# untitled.net
KiCad netlist of a schematic drawn in EAGLE
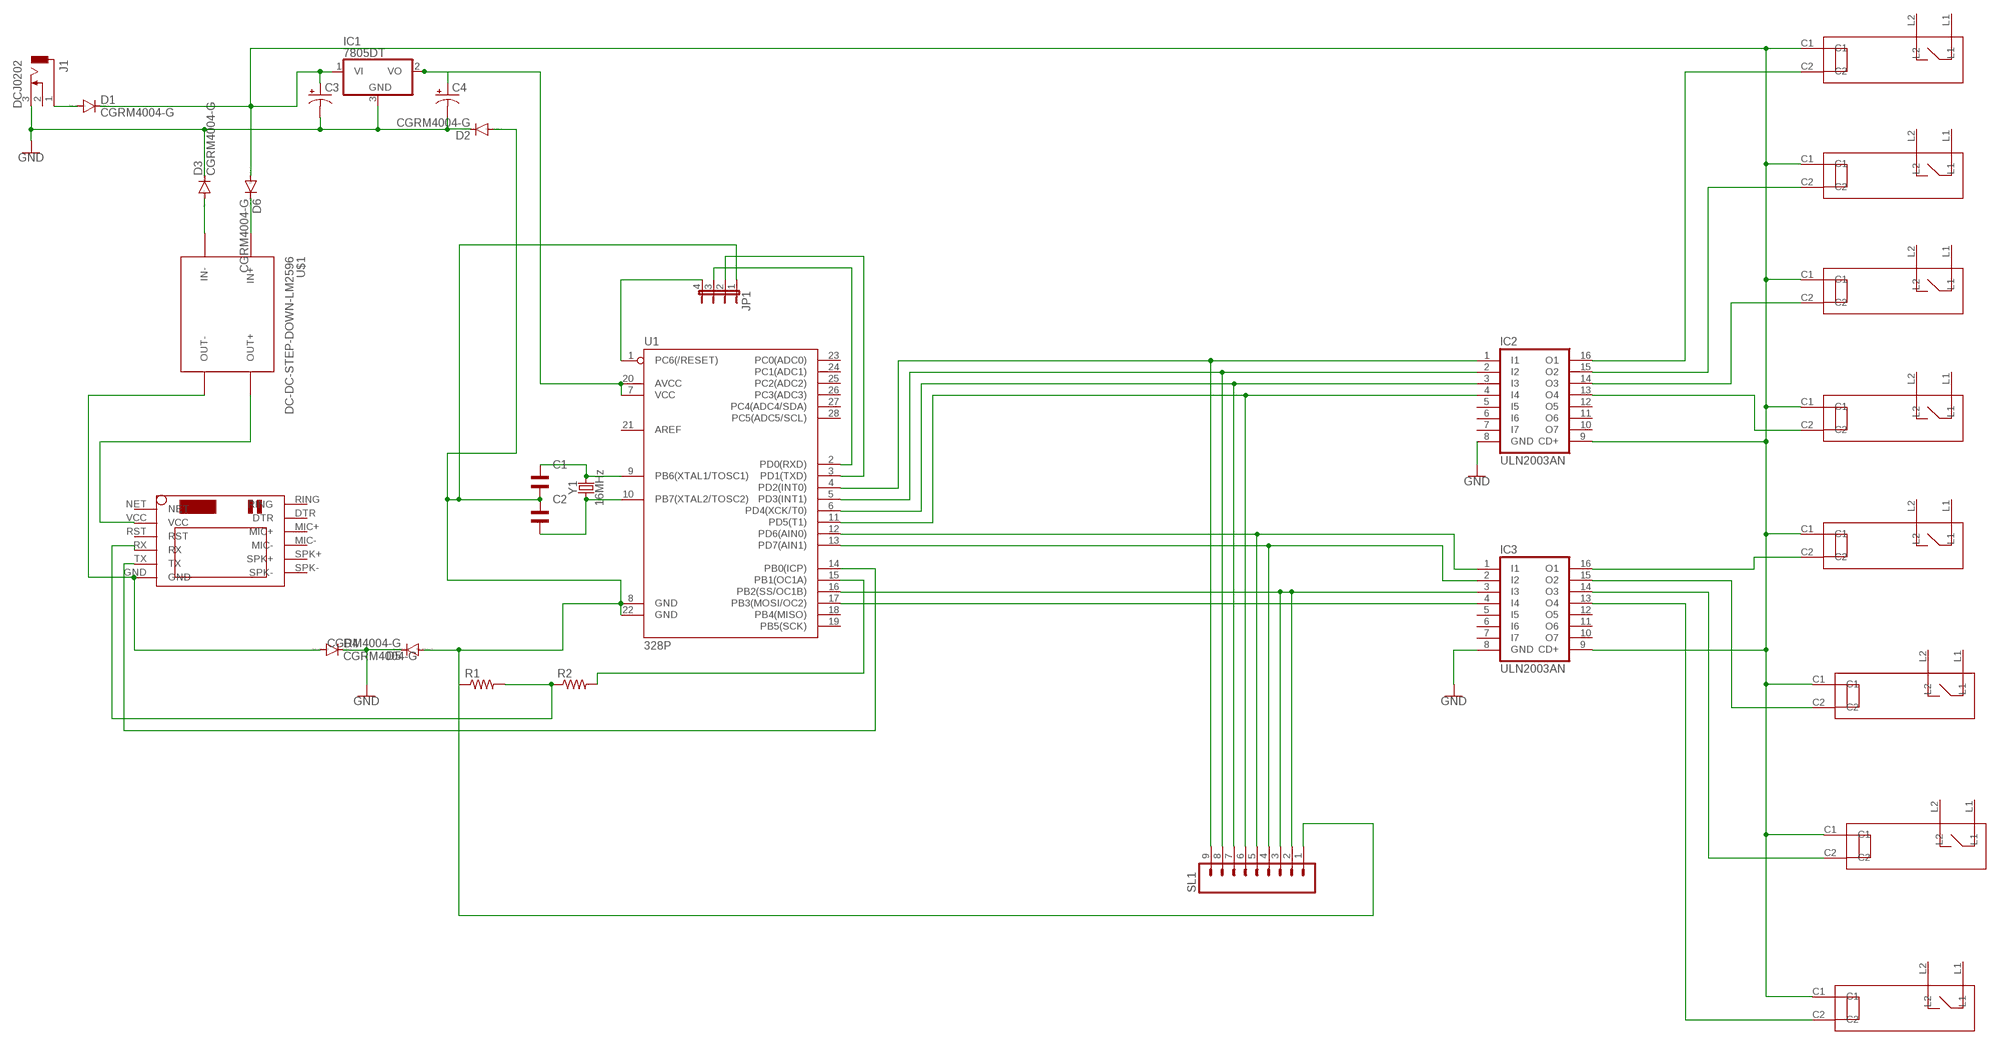
[diagram p0: schematic, sheet 1]

(export (version "E")
  (design (tool "Eeschema 10.0.6"))
  (components
    (comp (ref "C1")
      (value "WCAP-CSGP_1206_885012008001")
      (footprint "eagle-import:WCAP-CSGP_1206")
      (libsource (lib "eagle-import") (part "WCAP-CSGP_1206_885012008001"))
    )
    (comp (ref "C2")
      (value "WCAP-CSGP_1206_885012008001")
      (footprint "eagle-import:WCAP-CSGP_1206")
      (libsource (lib "eagle-import") (part "WCAP-CSGP_1206_885012008001"))
    )
    (comp (ref "C3")
      (value "CPOL-USE3.5-8")
      (footprint "eagle-import:E3,5-8")
      (libsource (lib "eagle-import") (part "CPOL-USE3.5-8"))
    )
    (comp (ref "C4")
      (value "CPOL-USE2.5-5")
      (footprint "eagle-import:E2,5-5")
      (libsource (lib "eagle-import") (part "CPOL-USE2.5-5"))
    )
    (comp (ref "D1")
      (value "CGRM4004-G")
      (footprint "eagle-import:SOD-123_MINI-SMA")
      (libsource (lib "eagle-import") (part "CGRM400-G4"))
    )
    (comp (ref "D2")
      (value "CGRM4004-G")
      (footprint "eagle-import:SOD-123_MINI-SMA")
      (libsource (lib "eagle-import") (part "CGRM400-G4"))
    )
    (comp (ref "D3")
      (value "CGRM4004-G")
      (footprint "eagle-import:SOD-123_MINI-SMA")
      (libsource (lib "eagle-import") (part "CGRM400-G4"))
    )
    (comp (ref "D4")
      (value "CGRM4004-G")
      (footprint "eagle-import:SOD-123_MINI-SMA")
      (libsource (lib "eagle-import") (part "CGRM400-G4"))
    )
    (comp (ref "D5")
      (value "CGRM4004-G")
      (footprint "eagle-import:SOD-123_MINI-SMA")
      (libsource (lib "eagle-import") (part "CGRM400-G4"))
    )
    (comp (ref "D6")
      (value "CGRM4004-G")
      (footprint "eagle-import:SOD-123_MINI-SMA")
      (libsource (lib "eagle-import") (part "CGRM400-G4"))
    )
    (comp (ref "IC1")
      (value "7805DT")
      (footprint "eagle-import:TO252")
      (libsource (lib "eagle-import") (part "78DT05"))
    )
    (comp (ref "IC2")
      (value "ULN2003AN")
      (footprint "eagle-import:DIL16")
      (libsource (lib "eagle-import") (part "ULN2003AN"))
    )
    (comp (ref "IC3")
      (value "ULN2003AN")
      (footprint "eagle-import:DIL16")
      (libsource (lib "eagle-import") (part "ULN2003AN"))
    )
    (comp (ref "J1")
      (value "DCJ0202")
      (footprint "eagle-import:DCJ0202")
      (libsource (lib "eagle-import") (part "DCJ0202"))
    )
    (comp (ref "JP1")
      (value "JP4E")
      (footprint "eagle-import:JP4")
      (libsource (lib "eagle-import") (part "JP4E"))
    )
    (comp (ref "R1")
      (value "R-US_R1206")
      (footprint "eagle-import:R1206")
      (libsource (lib "eagle-import") (part "R-US_R1206"))
    )
    (comp (ref "R2")
      (value "R-US_R1206")
      (footprint "eagle-import:R1206")
      (libsource (lib "eagle-import") (part "R-US_R1206"))
    )
    (comp (ref "SL1")
      (value "M09")
      (footprint "eagle-import:09P")
      (libsource (lib "eagle-import") (part "M09"))
    )
    (comp (ref "U$1")
      (value "DC-DC-STEP-DOWN-LM2596")
      (footprint "eagle-import:DC-DC-STEP-DOWN-LM2596")
      (libsource (lib "eagle-import") (part "DC-DC-STEP-DOWN-LM2596"))
    )
    (comp (ref "U$2")
      (value "SIM800LMODULE")
      (footprint "eagle-import:SIM800LMODULE")
      (libsource (lib "eagle-import") (part "SIM800LMODULE"))
    )
    (comp (ref "U$3")
      (value "HF46F")
      (footprint "eagle-import:HF46F")
      (libsource (lib "eagle-import") (part "HF46F"))
    )
    (comp (ref "U$4")
      (value "HF46F")
      (footprint "eagle-import:HF46F")
      (libsource (lib "eagle-import") (part "HF46F"))
    )
    (comp (ref "U$5")
      (value "HF46F")
      (footprint "eagle-import:HF46F")
      (libsource (lib "eagle-import") (part "HF46F"))
    )
    (comp (ref "U$6")
      (value "HF46F")
      (footprint "eagle-import:HF46F")
      (libsource (lib "eagle-import") (part "HF46F"))
    )
    (comp (ref "U$7")
      (value "HF46F")
      (footprint "eagle-import:HF46F")
      (libsource (lib "eagle-import") (part "HF46F"))
    )
    (comp (ref "U$8")
      (value "HF46F")
      (footprint "eagle-import:HF46F")
      (libsource (lib "eagle-import") (part "HF46F"))
    )
    (comp (ref "U$9")
      (value "HF46F")
      (footprint "eagle-import:HF46F")
      (libsource (lib "eagle-import") (part "HF46F"))
    )
    (comp (ref "U$10")
      (value "HF46F")
      (footprint "eagle-import:HF46F")
      (libsource (lib "eagle-import") (part "HF46F"))
    )
    (comp (ref "U1")
      (value "328P")
      (footprint "eagle-import:DIP28")
      (libsource (lib "eagle-import") (part "ATMEGA328P_PDIP"))
    )
    (comp (ref "Y1")
      (value "16MHz")
      (footprint "eagle-import:HC49US")
      (libsource (lib "eagle-import") (part "CRYSTAL-16MHZPTH-HC49US"))
    )
  )
  (nets
    (net (code "1") (name "GND") (class "Default")
      (node (ref "C3") (pin "-") (pinfunction "-_-") (pintype "passive"))
      (node (ref "C4") (pin "-") (pinfunction "-_-") (pintype "passive"))
      (node (ref "D2") (pin "C") (pinfunction "C_C") (pintype "passive"))
      (node (ref "D3") (pin "C") (pinfunction "C_C") (pintype "passive"))
      (node (ref "D4") (pin "C") (pinfunction "C_C") (pintype "passive"))
      (node (ref "D5") (pin "C") (pinfunction "C_C") (pintype "passive"))
      (node (ref "IC1") (pin "3") (pinfunction "GND_3") (pintype "passive"))
      (node (ref "IC2") (pin "8") (pinfunction "GND_8") (pintype "power_in"))
      (node (ref "IC3") (pin "8") (pinfunction "GND_8") (pintype "power_in"))
      (node (ref "J1") (pin "3") (pinfunction "3_3") (pintype "passive"))
    )
    (net (code "2") (name "Net-(C1-Pad1)") (class "Default")
      (node (ref "C1") (pin "1") (pinfunction "1_1") (pintype "passive"))
      (node (ref "C2") (pin "2") (pinfunction "2_2") (pintype "passive"))
      (node (ref "D2") (pin "A") (pinfunction "A_A") (pintype "passive"))
      (node (ref "D5") (pin "A") (pinfunction "A_A") (pintype "passive"))
      (node (ref "JP1") (pin "1") (pinfunction "1_1") (pintype "passive"))
      (node (ref "R1") (pin "1") (pinfunction "1_1") (pintype "passive"))
      (node (ref "SL1") (pin "1") (pinfunction "1_1") (pintype "passive"))
      (node (ref "U1") (pin "22") (pinfunction "GND_22") (pintype "bidirectional"))
      (node (ref "U1") (pin "8") (pinfunction "GND_8") (pintype "bidirectional"))
    )
    (net (code "3") (name "Net-(D1-PadA)") (class "Default")
      (node (ref "D1") (pin "A") (pinfunction "A_A") (pintype "passive"))
      (node (ref "J1") (pin "1") (pinfunction "1_1") (pintype "passive"))
    )
    (net (code "4") (name "Net-(D3-PadA)") (class "Default")
      (node (ref "D3") (pin "A") (pinfunction "A_A") (pintype "passive"))
      (node (ref "U$1") (pin "IN-") (pinfunction "IN-_IN-") (pintype "bidirectional"))
    )
    (net (code "5") (name "Net-(D4-PadA)") (class "Default")
      (node (ref "D4") (pin "A") (pinfunction "A_A") (pintype "passive"))
      (node (ref "U$1") (pin "OUT-") (pinfunction "OUT-_OUT-") (pintype "bidirectional"))
      (node (ref "U$2") (pin "GND") (pinfunction "GND_GND") (pintype "bidirectional"))
    )
    (net (code "6") (name "Net-(D6-PadC)") (class "Default")
      (node (ref "D6") (pin "C") (pinfunction "C_C") (pintype "passive"))
      (node (ref "U$1") (pin "IN+") (pinfunction "IN+_IN+") (pintype "bidirectional"))
    )
    (net (code "7") (name "Net-(IC1-VI)") (class "Default")
      (node (ref "C3") (pin "+") (pinfunction "+_+") (pintype "passive"))
      (node (ref "D1") (pin "C") (pinfunction "C_C") (pintype "passive"))
      (node (ref "D6") (pin "A") (pinfunction "A_A") (pintype "passive"))
      (node (ref "IC1") (pin "1") (pinfunction "VI_1") (pintype "input"))
      (node (ref "IC2") (pin "9") (pinfunction "CD+_9") (pintype "passive"))
      (node (ref "IC3") (pin "9") (pinfunction "CD+_9") (pintype "passive"))
      (node (ref "U$10") (pin "C1") (pinfunction "C1_C1") (pintype "bidirectional"))
      (node (ref "U$3") (pin "C1") (pinfunction "C1_C1") (pintype "bidirectional"))
      (node (ref "U$4") (pin "C1") (pinfunction "C1_C1") (pintype "bidirectional"))
      (node (ref "U$5") (pin "C1") (pinfunction "C1_C1") (pintype "bidirectional"))
      (node (ref "U$6") (pin "C1") (pinfunction "C1_C1") (pintype "bidirectional"))
      (node (ref "U$7") (pin "C1") (pinfunction "C1_C1") (pintype "bidirectional"))
      (node (ref "U$8") (pin "C1") (pinfunction "C1_C1") (pintype "bidirectional"))
      (node (ref "U$9") (pin "C1") (pinfunction "C1_C1") (pintype "bidirectional"))
    )
    (net (code "8") (name "Net-(IC1-VO)") (class "Default")
      (node (ref "C4") (pin "+") (pinfunction "+_+") (pintype "passive"))
      (node (ref "IC1") (pin "2") (pinfunction "VO_2") (pintype "passive"))
      (node (ref "U1") (pin "20") (pinfunction "AVCC_20") (pintype "bidirectional"))
      (node (ref "U1") (pin "7") (pinfunction "VCC_7") (pintype "bidirectional"))
    )
    (net (code "9") (name "Net-(IC2-I1)") (class "Default")
      (node (ref "IC2") (pin "1") (pinfunction "I1_1") (pintype "input"))
      (node (ref "SL1") (pin "9") (pinfunction "9_9") (pintype "passive"))
      (node (ref "U1") (pin "4") (pinfunction "PD2(INT0)_4") (pintype "bidirectional"))
    )
    (net (code "10") (name "Net-(IC2-I2)") (class "Default")
      (node (ref "IC2") (pin "2") (pinfunction "I2_2") (pintype "input"))
      (node (ref "SL1") (pin "8") (pinfunction "8_8") (pintype "passive"))
      (node (ref "U1") (pin "5") (pinfunction "PD3(INT1)_5") (pintype "bidirectional"))
    )
    (net (code "11") (name "Net-(IC2-I3)") (class "Default")
      (node (ref "IC2") (pin "3") (pinfunction "I3_3") (pintype "input"))
      (node (ref "SL1") (pin "7") (pinfunction "7_7") (pintype "passive"))
      (node (ref "U1") (pin "6") (pinfunction "PD4(XCK/T0)_6") (pintype "bidirectional"))
    )
    (net (code "12") (name "Net-(IC2-I4)") (class "Default")
      (node (ref "IC2") (pin "4") (pinfunction "I4_4") (pintype "input"))
      (node (ref "SL1") (pin "6") (pinfunction "6_6") (pintype "passive"))
      (node (ref "U1") (pin "11") (pinfunction "PD5(T1)_11") (pintype "bidirectional"))
    )
    (net (code "13") (name "Net-(IC2-O1)") (class "Default")
      (node (ref "IC2") (pin "16") (pinfunction "O1_16") (pintype "open_collector"))
      (node (ref "U$3") (pin "C2") (pinfunction "C2_C2") (pintype "bidirectional"))
    )
    (net (code "14") (name "Net-(IC2-O2)") (class "Default")
      (node (ref "IC2") (pin "15") (pinfunction "O2_15") (pintype "open_collector"))
      (node (ref "U$4") (pin "C2") (pinfunction "C2_C2") (pintype "bidirectional"))
    )
    (net (code "15") (name "Net-(IC2-O3)") (class "Default")
      (node (ref "IC2") (pin "14") (pinfunction "O3_14") (pintype "open_collector"))
      (node (ref "U$5") (pin "C2") (pinfunction "C2_C2") (pintype "bidirectional"))
    )
    (net (code "16") (name "Net-(IC2-O4)") (class "Default")
      (node (ref "IC2") (pin "13") (pinfunction "O4_13") (pintype "open_collector"))
      (node (ref "U$6") (pin "C2") (pinfunction "C2_C2") (pintype "bidirectional"))
    )
    (net (code "17") (name "Net-(IC3-I1)") (class "Default")
      (node (ref "IC3") (pin "1") (pinfunction "I1_1") (pintype "input"))
      (node (ref "SL1") (pin "5") (pinfunction "5_5") (pintype "passive"))
      (node (ref "U1") (pin "12") (pinfunction "PD6(AIN0)_12") (pintype "bidirectional"))
    )
    (net (code "18") (name "Net-(IC3-I2)") (class "Default")
      (node (ref "IC3") (pin "2") (pinfunction "I2_2") (pintype "input"))
      (node (ref "SL1") (pin "4") (pinfunction "4_4") (pintype "passive"))
      (node (ref "U1") (pin "13") (pinfunction "PD7(AIN1)_13") (pintype "bidirectional"))
    )
    (net (code "19") (name "Net-(IC3-I3)") (class "Default")
      (node (ref "IC3") (pin "3") (pinfunction "I3_3") (pintype "input"))
      (node (ref "SL1") (pin "2") (pinfunction "2_2") (pintype "passive"))
      (node (ref "SL1") (pin "3") (pinfunction "3_3") (pintype "passive"))
      (node (ref "U1") (pin "16") (pinfunction "PB2(SS/OC1B)_16") (pintype "bidirectional"))
    )
    (net (code "20") (name "Net-(IC3-I4)") (class "Default")
      (node (ref "IC3") (pin "4") (pinfunction "I4_4") (pintype "input"))
      (node (ref "U1") (pin "17") (pinfunction "PB3(MOSI/OC2)_17") (pintype "bidirectional"))
    )
    (net (code "21") (name "Net-(IC3-O1)") (class "Default")
      (node (ref "IC3") (pin "16") (pinfunction "O1_16") (pintype "open_collector"))
      (node (ref "U$7") (pin "C2") (pinfunction "C2_C2") (pintype "bidirectional"))
    )
    (net (code "22") (name "Net-(IC3-O2)") (class "Default")
      (node (ref "IC3") (pin "15") (pinfunction "O2_15") (pintype "open_collector"))
      (node (ref "U$8") (pin "C2") (pinfunction "C2_C2") (pintype "bidirectional"))
    )
    (net (code "23") (name "Net-(IC3-O3)") (class "Default")
      (node (ref "IC3") (pin "14") (pinfunction "O3_14") (pintype "open_collector"))
      (node (ref "U$9") (pin "C2") (pinfunction "C2_C2") (pintype "bidirectional"))
    )
    (net (code "24") (name "Net-(IC3-O4)") (class "Default")
      (node (ref "IC3") (pin "13") (pinfunction "O4_13") (pintype "open_collector"))
      (node (ref "U$10") (pin "C2") (pinfunction "C2_C2") (pintype "bidirectional"))
    )
    (net (code "25") (name "Net-(R1-Pad2)") (class "Default")
      (node (ref "R1") (pin "2") (pinfunction "2_2") (pintype "passive"))
      (node (ref "R2") (pin "1") (pinfunction "1_1") (pintype "passive"))
      (node (ref "U$2") (pin "RX") (pinfunction "RX_RX") (pintype "bidirectional"))
    )
    (net (code "26") (name "Net-(U$1-PadOUT+)") (class "Default")
      (node (ref "U$1") (pin "OUT+") (pinfunction "OUT+_OUT+") (pintype "bidirectional"))
      (node (ref "U$2") (pin "VCC") (pinfunction "VCC_VCC") (pintype "bidirectional"))
    )
    (net (code "27") (name "Net-(U1-PB0(ICP))") (class "Default")
      (node (ref "U$2") (pin "TX") (pinfunction "TX_TX") (pintype "bidirectional"))
      (node (ref "U1") (pin "14") (pinfunction "PB0(ICP)_14") (pintype "bidirectional"))
    )
    (net (code "28") (name "Net-(U1-PB1(OC1A))") (class "Default")
      (node (ref "R2") (pin "2") (pinfunction "2_2") (pintype "passive"))
      (node (ref "U1") (pin "15") (pinfunction "PB1(OC1A)_15") (pintype "bidirectional"))
    )
    (net (code "29") (name "Net-(U1-PB6(XTAL1{slash}TOSC1))") (class "Default")
      (node (ref "C1") (pin "2") (pinfunction "2_2") (pintype "passive"))
      (node (ref "U1") (pin "9") (pinfunction "PB6(XTAL1/TOSC1)_9") (pintype "bidirectional"))
      (node (ref "Y1") (pin "2") (pinfunction "2_2") (pintype "passive"))
    )
    (net (code "30") (name "Net-(U1-PB7(XTAL2{slash}TOSC2))") (class "Default")
      (node (ref "C2") (pin "1") (pinfunction "1_1") (pintype "passive"))
      (node (ref "U1") (pin "10") (pinfunction "PB7(XTAL2/TOSC2)_10") (pintype "bidirectional"))
      (node (ref "Y1") (pin "1") (pinfunction "1_1") (pintype "passive"))
    )
    (net (code "31") (name "Net-(U1-PC6({slash}RESET))") (class "Default")
      (node (ref "JP1") (pin "4") (pinfunction "4_4") (pintype "passive"))
      (node (ref "U1") (pin "1") (pinfunction "PC6(/RESET)_1") (pintype "bidirectional"))
    )
    (net (code "32") (name "Net-(U1-PD0(RXD))") (class "Default")
      (node (ref "JP1") (pin "3") (pinfunction "3_3") (pintype "passive"))
      (node (ref "U1") (pin "2") (pinfunction "PD0(RXD)_2") (pintype "bidirectional"))
    )
    (net (code "33") (name "Net-(U1-PD1(TXD))") (class "Default")
      (node (ref "JP1") (pin "2") (pinfunction "2_2") (pintype "passive"))
      (node (ref "U1") (pin "3") (pinfunction "PD1(TXD)_3") (pintype "bidirectional"))
    )
    (net (code "34") (name "unconnected-(IC2-I5-Pad5)") (class "Default")
      (node (ref "IC2") (pin "5") (pinfunction "I5_5") (pintype "input"))
    )
    (net (code "35") (name "unconnected-(IC2-I6-Pad6)") (class "Default")
      (node (ref "IC2") (pin "6") (pinfunction "I6_6") (pintype "input"))
    )
    (net (code "36") (name "unconnected-(IC2-I7-Pad7)") (class "Default")
      (node (ref "IC2") (pin "7") (pinfunction "I7_7") (pintype "input"))
    )
    (net (code "37") (name "unconnected-(IC2-O5-Pad12)") (class "Default")
      (node (ref "IC2") (pin "12") (pinfunction "O5_12") (pintype "open_collector"))
    )
    (net (code "38") (name "unconnected-(IC2-O6-Pad11)") (class "Default")
      (node (ref "IC2") (pin "11") (pinfunction "O6_11") (pintype "open_collector"))
    )
    (net (code "39") (name "unconnected-(IC2-O7-Pad10)") (class "Default")
      (node (ref "IC2") (pin "10") (pinfunction "O7_10") (pintype "open_collector"))
    )
    (net (code "40") (name "unconnected-(IC3-I5-Pad5)") (class "Default")
      (node (ref "IC3") (pin "5") (pinfunction "I5_5") (pintype "input"))
    )
    (net (code "41") (name "unconnected-(IC3-I6-Pad6)") (class "Default")
      (node (ref "IC3") (pin "6") (pinfunction "I6_6") (pintype "input"))
    )
    (net (code "42") (name "unconnected-(IC3-I7-Pad7)") (class "Default")
      (node (ref "IC3") (pin "7") (pinfunction "I7_7") (pintype "input"))
    )
    (net (code "43") (name "unconnected-(IC3-O5-Pad12)") (class "Default")
      (node (ref "IC3") (pin "12") (pinfunction "O5_12") (pintype "open_collector"))
    )
    (net (code "44") (name "unconnected-(IC3-O6-Pad11)") (class "Default")
      (node (ref "IC3") (pin "11") (pinfunction "O6_11") (pintype "open_collector"))
    )
    (net (code "45") (name "unconnected-(IC3-O7-Pad10)") (class "Default")
      (node (ref "IC3") (pin "10") (pinfunction "O7_10") (pintype "open_collector"))
    )
    (net (code "46") (name "unconnected-(J1-Pad2)") (class "Default")
      (node (ref "J1") (pin "2") (pinfunction "2_2") (pintype "passive"))
    )
    (net (code "47") (name "unconnected-(U$2-PadDTR)") (class "Default")
      (node (ref "U$2") (pin "DTR") (pinfunction "DTR_DTR") (pintype "bidirectional"))
    )
    (net (code "48") (name "unconnected-(U$2-PadMIC+)") (class "Default")
      (node (ref "U$2") (pin "MIC+") (pinfunction "MIC+_MIC+") (pintype "bidirectional"))
    )
    (net (code "49") (name "unconnected-(U$2-PadMIC-)") (class "Default")
      (node (ref "U$2") (pin "MIC-") (pinfunction "MIC-_MIC-") (pintype "bidirectional"))
    )
    (net (code "50") (name "unconnected-(U$2-PadNET)") (class "Default")
      (node (ref "U$2") (pin "NET") (pinfunction "NET_NET") (pintype "bidirectional"))
    )
    (net (code "51") (name "unconnected-(U$2-PadRING)") (class "Default")
      (node (ref "U$2") (pin "RING") (pinfunction "RING_RING") (pintype "bidirectional"))
    )
    (net (code "52") (name "unconnected-(U$2-PadRST)") (class "Default")
      (node (ref "U$2") (pin "RST") (pinfunction "RST_RST") (pintype "bidirectional"))
    )
    (net (code "53") (name "unconnected-(U$2-PadSPK+)") (class "Default")
      (node (ref "U$2") (pin "SPK+") (pinfunction "SPK+_SPK+") (pintype "bidirectional"))
    )
    (net (code "54") (name "unconnected-(U$2-PadSPK-)") (class "Default")
      (node (ref "U$2") (pin "SPK-") (pinfunction "SPK-_SPK-") (pintype "bidirectional"))
    )
    (net (code "55") (name "unconnected-(U$3-PadL1)") (class "Default")
      (node (ref "U$3") (pin "L1") (pinfunction "L1_L1") (pintype "bidirectional"))
    )
    (net (code "56") (name "unconnected-(U$3-PadL2)") (class "Default")
      (node (ref "U$3") (pin "L2") (pinfunction "L2_L2") (pintype "bidirectional"))
    )
    (net (code "57") (name "unconnected-(U$4-PadL1)") (class "Default")
      (node (ref "U$4") (pin "L1") (pinfunction "L1_L1") (pintype "bidirectional"))
    )
    (net (code "58") (name "unconnected-(U$4-PadL2)") (class "Default")
      (node (ref "U$4") (pin "L2") (pinfunction "L2_L2") (pintype "bidirectional"))
    )
    (net (code "59") (name "unconnected-(U$5-PadL1)") (class "Default")
      (node (ref "U$5") (pin "L1") (pinfunction "L1_L1") (pintype "bidirectional"))
    )
    (net (code "60") (name "unconnected-(U$5-PadL2)") (class "Default")
      (node (ref "U$5") (pin "L2") (pinfunction "L2_L2") (pintype "bidirectional"))
    )
    (net (code "61") (name "unconnected-(U$6-PadL1)") (class "Default")
      (node (ref "U$6") (pin "L1") (pinfunction "L1_L1") (pintype "bidirectional"))
    )
    (net (code "62") (name "unconnected-(U$6-PadL2)") (class "Default")
      (node (ref "U$6") (pin "L2") (pinfunction "L2_L2") (pintype "bidirectional"))
    )
    (net (code "63") (name "unconnected-(U$7-PadL1)") (class "Default")
      (node (ref "U$7") (pin "L1") (pinfunction "L1_L1") (pintype "bidirectional"))
    )
    (net (code "64") (name "unconnected-(U$7-PadL2)") (class "Default")
      (node (ref "U$7") (pin "L2") (pinfunction "L2_L2") (pintype "bidirectional"))
    )
    (net (code "65") (name "unconnected-(U$8-PadL1)") (class "Default")
      (node (ref "U$8") (pin "L1") (pinfunction "L1_L1") (pintype "bidirectional"))
    )
    (net (code "66") (name "unconnected-(U$8-PadL2)") (class "Default")
      (node (ref "U$8") (pin "L2") (pinfunction "L2_L2") (pintype "bidirectional"))
    )
    (net (code "67") (name "unconnected-(U$9-PadL1)") (class "Default")
      (node (ref "U$9") (pin "L1") (pinfunction "L1_L1") (pintype "bidirectional"))
    )
    (net (code "68") (name "unconnected-(U$9-PadL2)") (class "Default")
      (node (ref "U$9") (pin "L2") (pinfunction "L2_L2") (pintype "bidirectional"))
    )
    (net (code "69") (name "unconnected-(U$10-PadL1)") (class "Default")
      (node (ref "U$10") (pin "L1") (pinfunction "L1_L1") (pintype "bidirectional"))
    )
    (net (code "70") (name "unconnected-(U$10-PadL2)") (class "Default")
      (node (ref "U$10") (pin "L2") (pinfunction "L2_L2") (pintype "bidirectional"))
    )
    (net (code "71") (name "unconnected-(U1-AREF-Pad21)") (class "Default")
      (node (ref "U1") (pin "21") (pinfunction "AREF_21") (pintype "bidirectional"))
    )
    (net (code "72") (name "unconnected-(U1-PB4(MISO)-Pad18)") (class "Default")
      (node (ref "U1") (pin "18") (pinfunction "PB4(MISO)_18") (pintype "bidirectional"))
    )
    (net (code "73") (name "unconnected-(U1-PB5(SCK)-Pad19)") (class "Default")
      (node (ref "U1") (pin "19") (pinfunction "PB5(SCK)_19") (pintype "bidirectional"))
    )
    (net (code "74") (name "unconnected-(U1-PC0(ADC0)-Pad23)") (class "Default")
      (node (ref "U1") (pin "23") (pinfunction "PC0(ADC0)_23") (pintype "bidirectional"))
    )
    (net (code "75") (name "unconnected-(U1-PC1(ADC1)-Pad24)") (class "Default")
      (node (ref "U1") (pin "24") (pinfunction "PC1(ADC1)_24") (pintype "bidirectional"))
    )
    (net (code "76") (name "unconnected-(U1-PC2(ADC2)-Pad25)") (class "Default")
      (node (ref "U1") (pin "25") (pinfunction "PC2(ADC2)_25") (pintype "bidirectional"))
    )
    (net (code "77") (name "unconnected-(U1-PC3(ADC3)-Pad26)") (class "Default")
      (node (ref "U1") (pin "26") (pinfunction "PC3(ADC3)_26") (pintype "bidirectional"))
    )
    (net (code "78") (name "unconnected-(U1-PC4(ADC4{slash}SDA)-Pad27)") (class "Default")
      (node (ref "U1") (pin "27") (pinfunction "PC4(ADC4/SDA)_27") (pintype "bidirectional"))
    )
    (net (code "79") (name "unconnected-(U1-PC5(ADC5{slash}SCL)-Pad28)") (class "Default")
      (node (ref "U1") (pin "28") (pinfunction "PC5(ADC5/SCL)_28") (pintype "bidirectional"))
    )
  )
)
